# servoshield.net
KiCad netlist of a schematic drawn in EAGLE
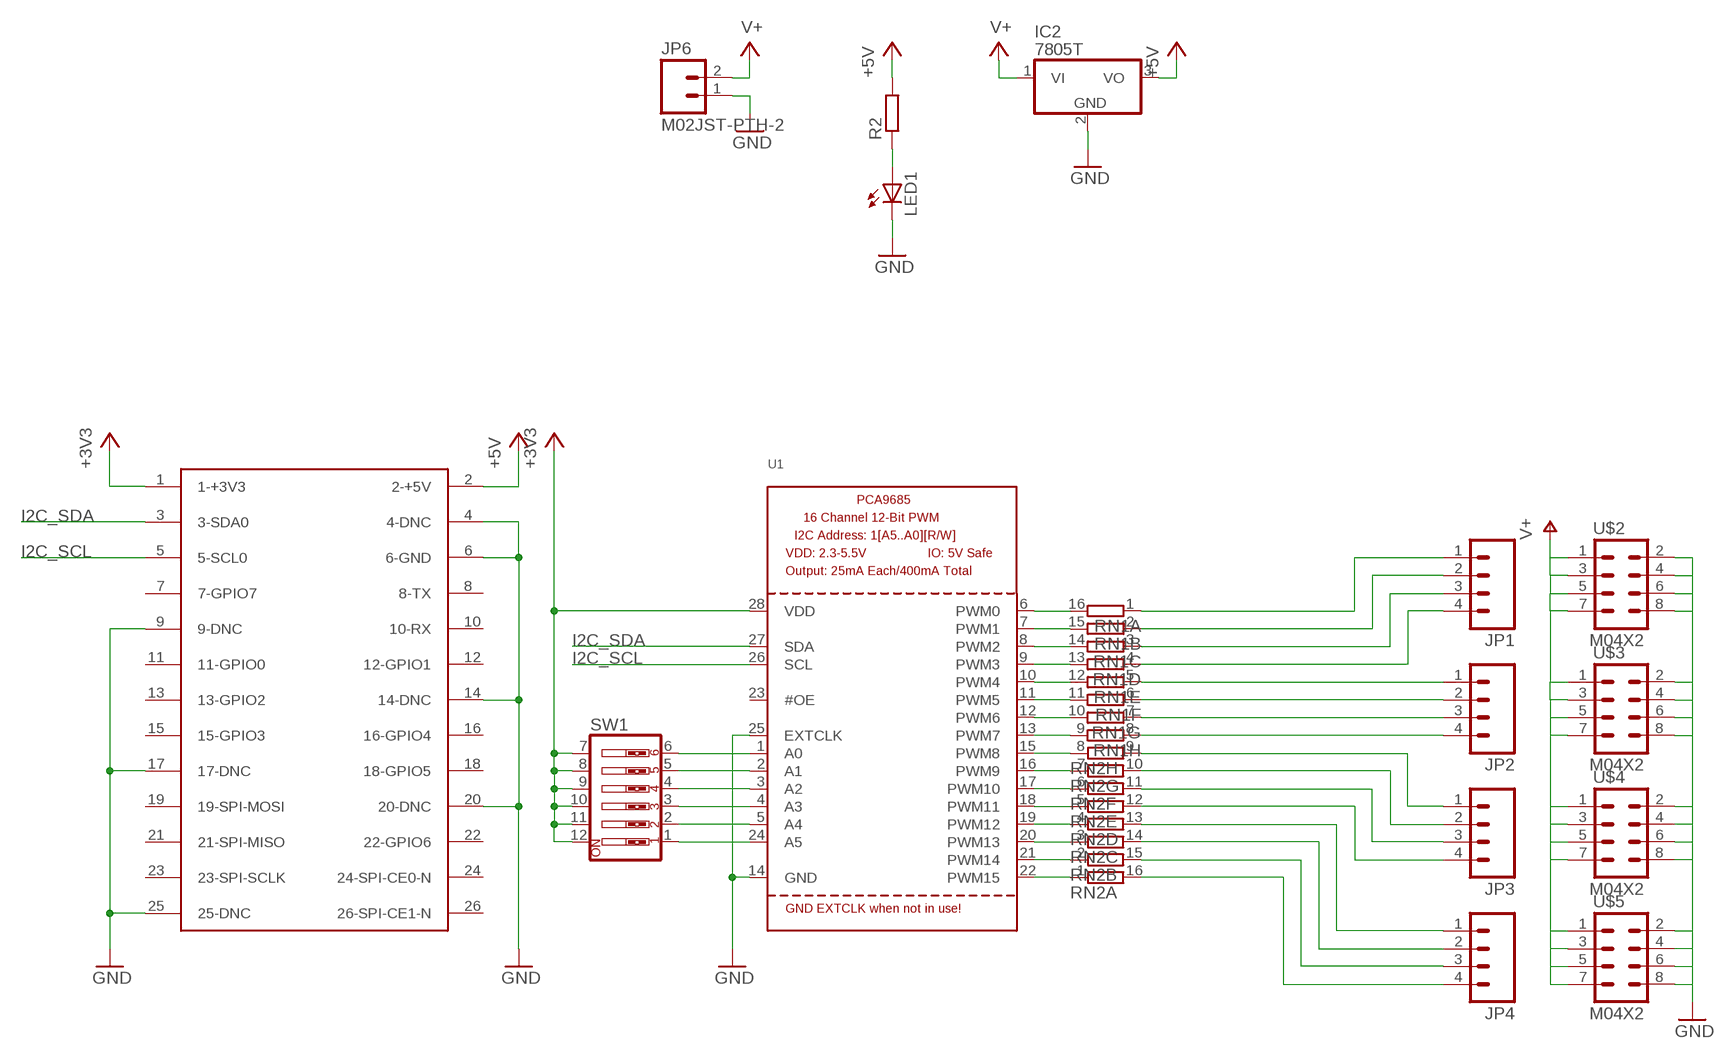
[diagram p0: schematic, sheet 1]

(export (version "E")
  (design (tool "Eeschema 10.0.6"))
  (components
    (comp (ref "IC2")
      (value "7805T")
      (footprint "eagle-import:TO220H")
      (libsource (lib "eagle-import") (part "78T05"))
    )
    (comp (ref "JP1")
      (value "M04PTH")
      (footprint "eagle-import:1X04")
      (libsource (lib "eagle-import") (part "M04PTH"))
    )
    (comp (ref "JP2")
      (value "M04PTH")
      (footprint "eagle-import:1X04")
      (libsource (lib "eagle-import") (part "M04PTH"))
    )
    (comp (ref "JP3")
      (value "M04PTH")
      (footprint "eagle-import:1X04")
      (libsource (lib "eagle-import") (part "M04PTH"))
    )
    (comp (ref "JP4")
      (value "M04PTH")
      (footprint "eagle-import:1X04")
      (libsource (lib "eagle-import") (part "M04PTH"))
    )
    (comp (ref "JP6")
      (value "M02JST-PTH-2")
      (footprint "eagle-import:JST-2-PTH")
      (libsource (lib "eagle-import") (part "M02JST-PTH-2"))
    )
    (comp (ref "LED1")
      (value "LED3MM")
      (footprint "eagle-import:LED3MM")
      (libsource (lib "eagle-import") (part "LED3MM"))
    )
    (comp (ref "R2")
      (value "R-EU_0207/7")
      (footprint "eagle-import:0207_7")
      (libsource (lib "eagle-import") (part "R-EU_0207/7"))
    )
    (comp (ref "RN1")
      (value "8R-N")
      (footprint "eagle-import:DIL16")
      (libsource (lib "eagle-import") (part "8R-N"))
    )
    (comp (ref "RN2")
      (value "8R-N")
      (footprint "eagle-import:DIL16")
      (libsource (lib "eagle-import") (part "8R-N"))
    )
    (comp (ref "SW1")
      (value "SW_DIP-6")
      (footprint "eagle-import:EDG-06")
      (libsource (lib "eagle-import") (part "SW_DIP-6"))
    )
    (comp (ref "U$1")
      (value "RASPBERRY-PI")
      (footprint "eagle-import:RASPBERRY-PI")
      (libsource (lib "eagle-import") (part "RASPBERRY-PI"))
    )
    (comp (ref "U$2")
      (value "M04X2")
      (footprint "eagle-import:2X4")
      (libsource (lib "eagle-import") (part "M04X2"))
    )
    (comp (ref "U$3")
      (value "M04X2")
      (footprint "eagle-import:2X4")
      (libsource (lib "eagle-import") (part "M04X2"))
    )
    (comp (ref "U$4")
      (value "M04X2")
      (footprint "eagle-import:2X4")
      (libsource (lib "eagle-import") (part "M04X2"))
    )
    (comp (ref "U$5")
      (value "M04X2")
      (footprint "eagle-import:2X4")
      (libsource (lib "eagle-import") (part "M04X2"))
    )
    (comp (ref "U1")
      (value "PCA9685")
      (footprint "eagle-import:TSSOP28")
      (libsource (lib "eagle-import") (part "PCA9685"))
    )
  )
  (nets
    (net (code "1") (name "+3V3") (class "Default")
      (node (ref "SW1") (pin "10") (pinfunction "10_10") (pintype "passive"))
      (node (ref "SW1") (pin "11") (pinfunction "11_11") (pintype "passive"))
      (node (ref "SW1") (pin "12") (pinfunction "12_12") (pintype "passive"))
      (node (ref "SW1") (pin "7") (pinfunction "7_7") (pintype "passive"))
      (node (ref "SW1") (pin "8") (pinfunction "8_8") (pintype "passive"))
      (node (ref "SW1") (pin "9") (pinfunction "9_9") (pintype "passive"))
      (node (ref "U$1") (pin "1") (pinfunction "1-+3V3_1") (pintype "bidirectional"))
      (node (ref "U1") (pin "28") (pinfunction "VDD_28") (pintype "power_in"))
    )
    (net (code "2") (name "+5V") (class "Default")
      (node (ref "IC2") (pin "3") (pinfunction "VO_3") (pintype "passive"))
      (node (ref "R2") (pin "2") (pinfunction "2_2") (pintype "passive"))
      (node (ref "U$1") (pin "2") (pinfunction "2-+5V_2") (pintype "bidirectional"))
    )
    (net (code "3") (name "/I2C_SCL") (class "Default")
      (node (ref "U$1") (pin "5") (pinfunction "5-SCL0_5") (pintype "bidirectional"))
      (node (ref "U1") (pin "26") (pinfunction "SCL_26") (pintype "bidirectional"))
    )
    (net (code "4") (name "/I2C_SDA") (class "Default")
      (node (ref "U$1") (pin "3") (pinfunction "3-SDA0_3") (pintype "bidirectional"))
      (node (ref "U1") (pin "27") (pinfunction "SDA_27") (pintype "bidirectional"))
    )
    (net (code "5") (name "GND") (class "Default")
      (node (ref "IC2") (pin "2") (pinfunction "GND_2") (pintype "passive"))
      (node (ref "JP6") (pin "1") (pinfunction "1_1") (pintype "passive"))
      (node (ref "LED1") (pin "K") (pinfunction "C_K") (pintype "passive"))
      (node (ref "U$1") (pin "14") (pinfunction "14-DNC_14") (pintype "bidirectional"))
      (node (ref "U$1") (pin "17") (pinfunction "17-DNC_17") (pintype "bidirectional"))
      (node (ref "U$1") (pin "20") (pinfunction "20-DNC_20") (pintype "bidirectional"))
      (node (ref "U$1") (pin "25") (pinfunction "25-DNC_25") (pintype "bidirectional"))
      (node (ref "U$1") (pin "4") (pinfunction "4-DNC_4") (pintype "bidirectional"))
      (node (ref "U$1") (pin "6") (pinfunction "6-GND_6") (pintype "bidirectional"))
      (node (ref "U$1") (pin "9") (pinfunction "9-DNC_9") (pintype "bidirectional"))
      (node (ref "U$2") (pin "2") (pinfunction "2_2") (pintype "passive"))
      (node (ref "U$2") (pin "4") (pinfunction "4_4") (pintype "passive"))
      (node (ref "U$2") (pin "6") (pinfunction "6_6") (pintype "passive"))
      (node (ref "U$2") (pin "8") (pinfunction "8_8") (pintype "passive"))
      (node (ref "U$3") (pin "2") (pinfunction "2_2") (pintype "passive"))
      (node (ref "U$3") (pin "4") (pinfunction "4_4") (pintype "passive"))
      (node (ref "U$3") (pin "6") (pinfunction "6_6") (pintype "passive"))
      (node (ref "U$3") (pin "8") (pinfunction "8_8") (pintype "passive"))
      (node (ref "U$4") (pin "2") (pinfunction "2_2") (pintype "passive"))
      (node (ref "U$4") (pin "4") (pinfunction "4_4") (pintype "passive"))
      (node (ref "U$4") (pin "6") (pinfunction "6_6") (pintype "passive"))
      (node (ref "U$4") (pin "8") (pinfunction "8_8") (pintype "passive"))
      (node (ref "U$5") (pin "2") (pinfunction "2_2") (pintype "passive"))
      (node (ref "U$5") (pin "4") (pinfunction "4_4") (pintype "passive"))
      (node (ref "U$5") (pin "6") (pinfunction "6_6") (pintype "passive"))
      (node (ref "U$5") (pin "8") (pinfunction "8_8") (pintype "passive"))
      (node (ref "U1") (pin "14") (pinfunction "GND_14") (pintype "power_in"))
      (node (ref "U1") (pin "25") (pinfunction "EXTCLK_25") (pintype "input"))
    )
    (net (code "6") (name "Net-(JP1-Pad1)") (class "Default")
      (node (ref "JP1") (pin "1") (pinfunction "1_1") (pintype "passive"))
      (node (ref "RN1") (pin "1") (pinfunction "1_1") (pintype "passive"))
    )
    (net (code "7") (name "Net-(LED1-PadA)") (class "Default")
      (node (ref "LED1") (pin "A") (pinfunction "A_A") (pintype "passive"))
      (node (ref "R2") (pin "1") (pinfunction "1_1") (pintype "passive"))
    )
    (net (code "8") (name "Net-(RN1A-2)") (class "Default")
      (node (ref "RN1") (pin "16") (pinfunction "2_16") (pintype "passive"))
      (node (ref "U1") (pin "6") (pinfunction "PWM0_6") (pintype "output"))
    )
    (net (code "9") (name "Net-(RN1B-1)") (class "Default")
      (node (ref "JP1") (pin "2") (pinfunction "2_2") (pintype "passive"))
      (node (ref "RN1") (pin "2") (pinfunction "1_2") (pintype "passive"))
    )
    (net (code "10") (name "Net-(RN1B-2)") (class "Default")
      (node (ref "RN1") (pin "15") (pinfunction "2_15") (pintype "passive"))
      (node (ref "U1") (pin "7") (pinfunction "PWM1_7") (pintype "output"))
    )
    (net (code "11") (name "Net-(RN1C-1)") (class "Default")
      (node (ref "JP1") (pin "3") (pinfunction "3_3") (pintype "passive"))
      (node (ref "RN1") (pin "3") (pinfunction "1_3") (pintype "passive"))
    )
    (net (code "12") (name "Net-(RN1C-2)") (class "Default")
      (node (ref "RN1") (pin "14") (pinfunction "2_14") (pintype "passive"))
      (node (ref "U1") (pin "8") (pinfunction "PWM2_8") (pintype "output"))
    )
    (net (code "13") (name "Net-(RN1D-1)") (class "Default")
      (node (ref "JP1") (pin "4") (pinfunction "4_4") (pintype "passive"))
      (node (ref "RN1") (pin "4") (pinfunction "1_4") (pintype "passive"))
    )
    (net (code "14") (name "Net-(RN1D-2)") (class "Default")
      (node (ref "RN1") (pin "13") (pinfunction "2_13") (pintype "passive"))
      (node (ref "U1") (pin "9") (pinfunction "PWM3_9") (pintype "output"))
    )
    (net (code "15") (name "Net-(RN1E-1)") (class "Default")
      (node (ref "JP2") (pin "1") (pinfunction "1_1") (pintype "passive"))
      (node (ref "RN1") (pin "5") (pinfunction "1_5") (pintype "passive"))
    )
    (net (code "16") (name "Net-(RN1E-2)") (class "Default")
      (node (ref "RN1") (pin "12") (pinfunction "2_12") (pintype "passive"))
      (node (ref "U1") (pin "10") (pinfunction "PWM4_10") (pintype "output"))
    )
    (net (code "17") (name "Net-(RN1F-1)") (class "Default")
      (node (ref "JP2") (pin "2") (pinfunction "2_2") (pintype "passive"))
      (node (ref "RN1") (pin "6") (pinfunction "1_6") (pintype "passive"))
    )
    (net (code "18") (name "Net-(RN1F-2)") (class "Default")
      (node (ref "RN1") (pin "11") (pinfunction "2_11") (pintype "passive"))
      (node (ref "U1") (pin "11") (pinfunction "PWM5_11") (pintype "output"))
    )
    (net (code "19") (name "Net-(RN1G-1)") (class "Default")
      (node (ref "JP2") (pin "3") (pinfunction "3_3") (pintype "passive"))
      (node (ref "RN1") (pin "7") (pinfunction "1_7") (pintype "passive"))
    )
    (net (code "20") (name "Net-(RN1G-2)") (class "Default")
      (node (ref "RN1") (pin "10") (pinfunction "2_10") (pintype "passive"))
      (node (ref "U1") (pin "12") (pinfunction "PWM6_12") (pintype "output"))
    )
    (net (code "21") (name "Net-(RN1H-1)") (class "Default")
      (node (ref "JP2") (pin "4") (pinfunction "4_4") (pintype "passive"))
      (node (ref "RN1") (pin "8") (pinfunction "1_8") (pintype "passive"))
    )
    (net (code "22") (name "Net-(RN1H-2)") (class "Default")
      (node (ref "RN1") (pin "9") (pinfunction "2_9") (pintype "passive"))
      (node (ref "U1") (pin "13") (pinfunction "PWM7_13") (pintype "output"))
    )
    (net (code "23") (name "Net-(RN2A-2)") (class "Default")
      (node (ref "JP4") (pin "4") (pinfunction "4_4") (pintype "passive"))
      (node (ref "RN2") (pin "16") (pinfunction "2_16") (pintype "passive"))
    )
    (net (code "24") (name "Net-(RN2B-1)") (class "Default")
      (node (ref "RN2") (pin "2") (pinfunction "1_2") (pintype "passive"))
      (node (ref "U1") (pin "21") (pinfunction "PWM14_21") (pintype "output"))
    )
    (net (code "25") (name "Net-(RN2B-2)") (class "Default")
      (node (ref "JP4") (pin "3") (pinfunction "3_3") (pintype "passive"))
      (node (ref "RN2") (pin "15") (pinfunction "2_15") (pintype "passive"))
    )
    (net (code "26") (name "Net-(RN2C-1)") (class "Default")
      (node (ref "RN2") (pin "3") (pinfunction "1_3") (pintype "passive"))
      (node (ref "U1") (pin "20") (pinfunction "PWM13_20") (pintype "output"))
    )
    (net (code "27") (name "Net-(RN2C-2)") (class "Default")
      (node (ref "JP4") (pin "2") (pinfunction "2_2") (pintype "passive"))
      (node (ref "RN2") (pin "14") (pinfunction "2_14") (pintype "passive"))
    )
    (net (code "28") (name "Net-(RN2D-1)") (class "Default")
      (node (ref "RN2") (pin "4") (pinfunction "1_4") (pintype "passive"))
      (node (ref "U1") (pin "19") (pinfunction "PWM12_19") (pintype "output"))
    )
    (net (code "29") (name "Net-(RN2D-2)") (class "Default")
      (node (ref "JP4") (pin "1") (pinfunction "1_1") (pintype "passive"))
      (node (ref "RN2") (pin "13") (pinfunction "2_13") (pintype "passive"))
    )
    (net (code "30") (name "Net-(RN2E-1)") (class "Default")
      (node (ref "RN2") (pin "5") (pinfunction "1_5") (pintype "passive"))
      (node (ref "U1") (pin "18") (pinfunction "PWM11_18") (pintype "output"))
    )
    (net (code "31") (name "Net-(RN2E-2)") (class "Default")
      (node (ref "JP3") (pin "4") (pinfunction "4_4") (pintype "passive"))
      (node (ref "RN2") (pin "12") (pinfunction "2_12") (pintype "passive"))
    )
    (net (code "32") (name "Net-(RN2F-1)") (class "Default")
      (node (ref "RN2") (pin "6") (pinfunction "1_6") (pintype "passive"))
      (node (ref "U1") (pin "17") (pinfunction "PWM10_17") (pintype "output"))
    )
    (net (code "33") (name "Net-(RN2F-2)") (class "Default")
      (node (ref "JP3") (pin "3") (pinfunction "3_3") (pintype "passive"))
      (node (ref "RN2") (pin "11") (pinfunction "2_11") (pintype "passive"))
    )
    (net (code "34") (name "Net-(RN2G-1)") (class "Default")
      (node (ref "RN2") (pin "7") (pinfunction "1_7") (pintype "passive"))
      (node (ref "U1") (pin "16") (pinfunction "PWM9_16") (pintype "output"))
    )
    (net (code "35") (name "Net-(RN2G-2)") (class "Default")
      (node (ref "JP3") (pin "2") (pinfunction "2_2") (pintype "passive"))
      (node (ref "RN2") (pin "10") (pinfunction "2_10") (pintype "passive"))
    )
    (net (code "36") (name "Net-(RN2H-1)") (class "Default")
      (node (ref "RN2") (pin "8") (pinfunction "1_8") (pintype "passive"))
      (node (ref "U1") (pin "15") (pinfunction "PWM8_15") (pintype "output"))
    )
    (net (code "37") (name "Net-(RN2H-2)") (class "Default")
      (node (ref "JP3") (pin "1") (pinfunction "1_1") (pintype "passive"))
      (node (ref "RN2") (pin "9") (pinfunction "2_9") (pintype "passive"))
    )
    (net (code "38") (name "Net-(U1-A0)") (class "Default")
      (node (ref "SW1") (pin "6") (pinfunction "6_6") (pintype "passive"))
      (node (ref "U1") (pin "1") (pinfunction "A0_1") (pintype "bidirectional"))
    )
    (net (code "39") (name "Net-(U1-A1)") (class "Default")
      (node (ref "SW1") (pin "5") (pinfunction "5_5") (pintype "passive"))
      (node (ref "U1") (pin "2") (pinfunction "A1_2") (pintype "bidirectional"))
    )
    (net (code "40") (name "Net-(U1-A2)") (class "Default")
      (node (ref "SW1") (pin "4") (pinfunction "4_4") (pintype "passive"))
      (node (ref "U1") (pin "3") (pinfunction "A2_3") (pintype "bidirectional"))
    )
    (net (code "41") (name "Net-(U1-A3)") (class "Default")
      (node (ref "SW1") (pin "3") (pinfunction "3_3") (pintype "passive"))
      (node (ref "U1") (pin "4") (pinfunction "A3_4") (pintype "bidirectional"))
    )
    (net (code "42") (name "Net-(U1-A4)") (class "Default")
      (node (ref "SW1") (pin "2") (pinfunction "2_2") (pintype "passive"))
      (node (ref "U1") (pin "5") (pinfunction "A4_5") (pintype "bidirectional"))
    )
    (net (code "43") (name "Net-(U1-A5)") (class "Default")
      (node (ref "SW1") (pin "1") (pinfunction "1_1") (pintype "passive"))
      (node (ref "U1") (pin "24") (pinfunction "A5_24") (pintype "bidirectional"))
    )
    (net (code "44") (name "Net-(U1-PWM15)") (class "Default")
      (node (ref "RN2") (pin "1") (pinfunction "1_1") (pintype "passive"))
      (node (ref "U1") (pin "22") (pinfunction "PWM15_22") (pintype "output"))
    )
    (net (code "45") (name "V+") (class "Default")
      (node (ref "IC2") (pin "1") (pinfunction "VI_1") (pintype "input"))
      (node (ref "JP6") (pin "2") (pinfunction "2_2") (pintype "passive"))
      (node (ref "U$2") (pin "1") (pinfunction "1_1") (pintype "passive"))
      (node (ref "U$2") (pin "3") (pinfunction "3_3") (pintype "passive"))
      (node (ref "U$2") (pin "5") (pinfunction "5_5") (pintype "passive"))
      (node (ref "U$2") (pin "7") (pinfunction "7_7") (pintype "passive"))
      (node (ref "U$3") (pin "1") (pinfunction "1_1") (pintype "passive"))
      (node (ref "U$3") (pin "3") (pinfunction "3_3") (pintype "passive"))
      (node (ref "U$3") (pin "5") (pinfunction "5_5") (pintype "passive"))
      (node (ref "U$3") (pin "7") (pinfunction "7_7") (pintype "passive"))
      (node (ref "U$4") (pin "1") (pinfunction "1_1") (pintype "passive"))
      (node (ref "U$4") (pin "3") (pinfunction "3_3") (pintype "passive"))
      (node (ref "U$4") (pin "5") (pinfunction "5_5") (pintype "passive"))
      (node (ref "U$4") (pin "7") (pinfunction "7_7") (pintype "passive"))
      (node (ref "U$5") (pin "1") (pinfunction "1_1") (pintype "passive"))
      (node (ref "U$5") (pin "3") (pinfunction "3_3") (pintype "passive"))
      (node (ref "U$5") (pin "5") (pinfunction "5_5") (pintype "passive"))
      (node (ref "U$5") (pin "7") (pinfunction "7_7") (pintype "passive"))
    )
    (net (code "46") (name "unconnected-(U$1-7-GPIO7-Pad7)") (class "Default")
      (node (ref "U$1") (pin "7") (pinfunction "7-GPIO7_7") (pintype "bidirectional"))
    )
    (net (code "47") (name "unconnected-(U$1-8-TX-Pad8)") (class "Default")
      (node (ref "U$1") (pin "8") (pinfunction "8-TX_8") (pintype "bidirectional"))
    )
    (net (code "48") (name "unconnected-(U$1-10-RX-Pad10)") (class "Default")
      (node (ref "U$1") (pin "10") (pinfunction "10-RX_10") (pintype "bidirectional"))
    )
    (net (code "49") (name "unconnected-(U$1-11-GPIO0-Pad11)") (class "Default")
      (node (ref "U$1") (pin "11") (pinfunction "11-GPIO0_11") (pintype "bidirectional"))
    )
    (net (code "50") (name "unconnected-(U$1-12-GPIO1-Pad12)") (class "Default")
      (node (ref "U$1") (pin "12") (pinfunction "12-GPIO1_12") (pintype "bidirectional"))
    )
    (net (code "51") (name "unconnected-(U$1-13-GPIO2-Pad13)") (class "Default")
      (node (ref "U$1") (pin "13") (pinfunction "13-GPIO2_13") (pintype "bidirectional"))
    )
    (net (code "52") (name "unconnected-(U$1-15-GPIO3-Pad15)") (class "Default")
      (node (ref "U$1") (pin "15") (pinfunction "15-GPIO3_15") (pintype "bidirectional"))
    )
    (net (code "53") (name "unconnected-(U$1-16-GPIO4-Pad16)") (class "Default")
      (node (ref "U$1") (pin "16") (pinfunction "16-GPIO4_16") (pintype "bidirectional"))
    )
    (net (code "54") (name "unconnected-(U$1-18-GPIO5-Pad18)") (class "Default")
      (node (ref "U$1") (pin "18") (pinfunction "18-GPIO5_18") (pintype "bidirectional"))
    )
    (net (code "55") (name "unconnected-(U$1-19-SPI-MOSI-Pad19)") (class "Default")
      (node (ref "U$1") (pin "19") (pinfunction "19-SPI-MOSI_19") (pintype "bidirectional"))
    )
    (net (code "56") (name "unconnected-(U$1-21-SPI-MISO-Pad21)") (class "Default")
      (node (ref "U$1") (pin "21") (pinfunction "21-SPI-MISO_21") (pintype "bidirectional"))
    )
    (net (code "57") (name "unconnected-(U$1-22-GPIO6-Pad22)") (class "Default")
      (node (ref "U$1") (pin "22") (pinfunction "22-GPIO6_22") (pintype "bidirectional"))
    )
    (net (code "58") (name "unconnected-(U$1-23-SPI-SCLK-Pad23)") (class "Default")
      (node (ref "U$1") (pin "23") (pinfunction "23-SPI-SCLK_23") (pintype "bidirectional"))
    )
    (net (code "59") (name "unconnected-(U$1-24-SPI-CE0-N-Pad24)") (class "Default")
      (node (ref "U$1") (pin "24") (pinfunction "24-SPI-CE0-N_24") (pintype "bidirectional"))
    )
    (net (code "60") (name "unconnected-(U$1-26-SPI-CE1-N-Pad26)") (class "Default")
      (node (ref "U$1") (pin "26") (pinfunction "26-SPI-CE1-N_26") (pintype "bidirectional"))
    )
    (net (code "61") (name "unconnected-(U1-#OE-Pad23)") (class "Default")
      (node (ref "U1") (pin "23") (pinfunction "#OE_23") (pintype "input"))
    )
  )
)
